# psu.net
KiCad netlist of a schematic drawn in EAGLE
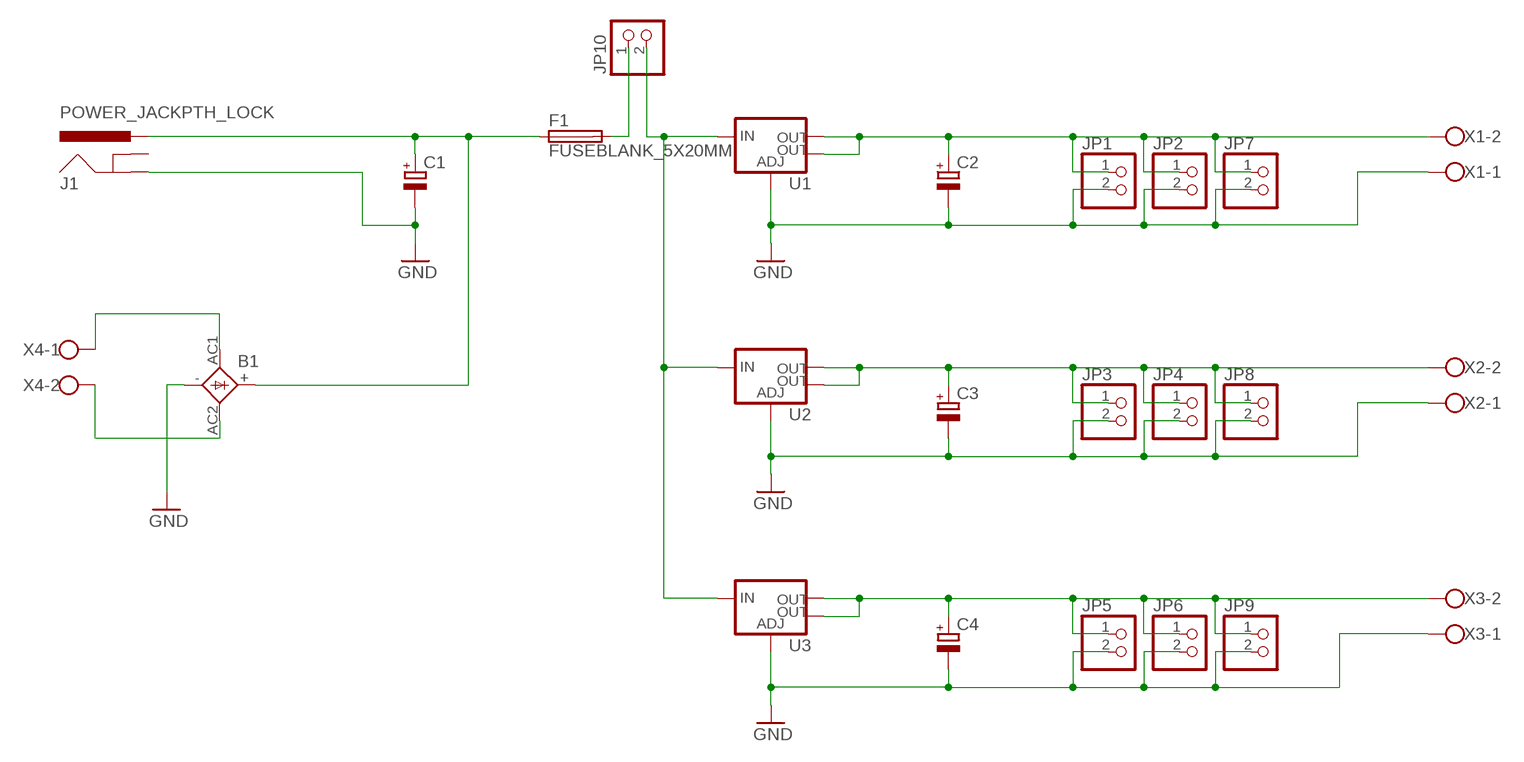
[diagram p0: schematic, sheet 1]

(export (version "E")
  (design (tool "Eeschema 10.0.6"))
  (components
    (comp (ref "B1")
      (value "KBU")
      (footprint "eagle-import:KBU")
      (libsource (lib "eagle-import") (part "KBU"))
    )
    (comp (ref "C1")
      (value "CPOL-EUE5-10.5")
      (footprint "eagle-import:E5-10,5")
      (libsource (lib "eagle-import") (part "resistor_CPOL-EUE5-10.5"))
    )
    (comp (ref "C2")
      (value "CPOL-EUE2.5-7")
      (footprint "eagle-import:E2,5-7")
      (libsource (lib "eagle-import") (part "CPOL-EUE2.5-7"))
    )
    (comp (ref "C3")
      (value "CPOL-EUE2.5-7")
      (footprint "eagle-import:E2,5-7")
      (libsource (lib "eagle-import") (part "CPOL-EUE2.5-7"))
    )
    (comp (ref "C4")
      (value "CPOL-EUE2.5-7")
      (footprint "eagle-import:E2,5-7")
      (libsource (lib "eagle-import") (part "CPOL-EUE2.5-7"))
    )
    (comp (ref "F1")
      (value "FUSEBLANK_5X20MM")
      (footprint "eagle-import:FUSE_HOLDER_5X20MM")
      (libsource (lib "eagle-import") (part "FUSEBLANK_5X20MM"))
    )
    (comp (ref "J1")
      (value "POWER_JACKPTH_LOCK")
      (footprint "eagle-import:POWER_JACK_PTH_LOCK")
      (libsource (lib "eagle-import") (part "POWER_JACKPTH_LOCK"))
    )
    (comp (ref "JP1")
      (value "PINHD-1X2")
      (footprint "eagle-import:1X02")
      (libsource (lib "eagle-import") (part "PINHD-1X2"))
    )
    (comp (ref "JP2")
      (value "PINHD-1X2")
      (footprint "eagle-import:1X02")
      (libsource (lib "eagle-import") (part "PINHD-1X2"))
    )
    (comp (ref "JP3")
      (value "PINHD-1X2")
      (footprint "eagle-import:1X02")
      (libsource (lib "eagle-import") (part "PINHD-1X2"))
    )
    (comp (ref "JP4")
      (value "PINHD-1X2")
      (footprint "eagle-import:1X02")
      (libsource (lib "eagle-import") (part "PINHD-1X2"))
    )
    (comp (ref "JP5")
      (value "PINHD-1X2")
      (footprint "eagle-import:1X02")
      (libsource (lib "eagle-import") (part "PINHD-1X2"))
    )
    (comp (ref "JP6")
      (value "PINHD-1X2")
      (footprint "eagle-import:1X02")
      (libsource (lib "eagle-import") (part "PINHD-1X2"))
    )
    (comp (ref "JP7")
      (value "PINHD-1X2")
      (footprint "eagle-import:1X02")
      (libsource (lib "eagle-import") (part "PINHD-1X2"))
    )
    (comp (ref "JP8")
      (value "PINHD-1X2")
      (footprint "eagle-import:1X02")
      (libsource (lib "eagle-import") (part "PINHD-1X2"))
    )
    (comp (ref "JP9")
      (value "PINHD-1X2")
      (footprint "eagle-import:1X02")
      (libsource (lib "eagle-import") (part "PINHD-1X2"))
    )
    (comp (ref "JP10")
      (value "PINHD-1X2")
      (footprint "eagle-import:1X02")
      (libsource (lib "eagle-import") (part "PINHD-1X2"))
    )
    (comp (ref "U1")
      (value "V_REG_LM1117SOT223")
      (footprint "eagle-import:SOT223")
      (libsource (lib "eagle-import") (part "V_REG_LM1117SOT223"))
    )
    (comp (ref "U2")
      (value "V_REG_LM1117SOT223")
      (footprint "eagle-import:SOT223")
      (libsource (lib "eagle-import") (part "V_REG_LM1117SOT223"))
    )
    (comp (ref "U3")
      (value "V_REG_LM1117SOT223")
      (footprint "eagle-import:SOT223")
      (libsource (lib "eagle-import") (part "V_REG_LM1117SOT223"))
    )
    (comp (ref "X1")
      (value "W237-102")
      (footprint "eagle-import:W237-102")
      (fields (field (name "MPN") "237-102"))
      (libsource (lib "eagle-import") (part "W237-102"))
    )
    (comp (ref "X2")
      (value "W237-102")
      (footprint "eagle-import:W237-102")
      (fields (field (name "MPN") "237-102"))
      (libsource (lib "eagle-import") (part "W237-102"))
    )
    (comp (ref "X3")
      (value "W237-102")
      (footprint "eagle-import:W237-102")
      (fields (field (name "MPN") "237-102"))
      (libsource (lib "eagle-import") (part "W237-102"))
    )
    (comp (ref "X4")
      (value "W237-102")
      (footprint "eagle-import:W237-102")
      (fields (field (name "MPN") "237-102"))
      (libsource (lib "eagle-import") (part "W237-102"))
    )
  )
  (nets
    (net (code "1") (name "GND") (class "Default")
      (node (ref "B1") (pin "-") (pinfunction "-_-") (pintype "passive"))
      (node (ref "C1") (pin "-") (pinfunction "-_-") (pintype "passive"))
      (node (ref "C2") (pin "-") (pinfunction "-_-") (pintype "passive"))
      (node (ref "C3") (pin "-") (pinfunction "-_-") (pintype "passive"))
      (node (ref "C4") (pin "-") (pinfunction "-_-") (pintype "passive"))
      (node (ref "J1") (pin "GND") (pinfunction "GND_GND") (pintype "bidirectional"))
      (node (ref "JP1") (pin "2") (pinfunction "2_2") (pintype "passive"))
      (node (ref "JP2") (pin "2") (pinfunction "2_2") (pintype "passive"))
      (node (ref "JP3") (pin "2") (pinfunction "2_2") (pintype "passive"))
      (node (ref "JP4") (pin "2") (pinfunction "2_2") (pintype "passive"))
      (node (ref "JP5") (pin "2") (pinfunction "2_2") (pintype "passive"))
      (node (ref "JP6") (pin "2") (pinfunction "2_2") (pintype "passive"))
      (node (ref "JP7") (pin "2") (pinfunction "2_2") (pintype "passive"))
      (node (ref "JP8") (pin "2") (pinfunction "2_2") (pintype "passive"))
      (node (ref "JP9") (pin "2") (pinfunction "2_2") (pintype "passive"))
      (node (ref "U1") (pin "1") (pinfunction "ADJ_1") (pintype "input"))
      (node (ref "U2") (pin "1") (pinfunction "ADJ_1") (pintype "input"))
      (node (ref "U3") (pin "1") (pinfunction "ADJ_1") (pintype "input"))
      (node (ref "X1") (pin "1") (pinfunction "KL_1") (pintype "passive"))
      (node (ref "X2") (pin "1") (pinfunction "KL_1") (pintype "passive"))
      (node (ref "X3") (pin "1") (pinfunction "KL_1") (pintype "passive"))
    )
    (net (code "2") (name "Net-(B1-Pad+)") (class "Default")
      (node (ref "B1") (pin "+") (pinfunction "+_+") (pintype "passive"))
      (node (ref "C1") (pin "+") (pinfunction "+_+") (pintype "passive"))
      (node (ref "F1") (pin "1") (pinfunction "1_1") (pintype "passive"))
      (node (ref "J1") (pin "PWR") (pinfunction "PWR_PWR") (pintype "bidirectional"))
    )
    (net (code "3") (name "Net-(F1-Pad2)") (class "Default")
      (node (ref "F1") (pin "2") (pinfunction "2_2") (pintype "passive"))
      (node (ref "JP10") (pin "1") (pinfunction "1_1") (pintype "passive"))
    )
    (net (code "4") (name "Net-(U1-IN)") (class "Default")
      (node (ref "JP10") (pin "2") (pinfunction "2_2") (pintype "passive"))
      (node (ref "U1") (pin "3") (pinfunction "IN_3") (pintype "input"))
      (node (ref "U2") (pin "3") (pinfunction "IN_3") (pintype "input"))
      (node (ref "U3") (pin "3") (pinfunction "IN_3") (pintype "input"))
    )
    (net (code "5") (name "Net-(X1B-KL)") (class "Default")
      (node (ref "C2") (pin "+") (pinfunction "+_+") (pintype "passive"))
      (node (ref "JP1") (pin "1") (pinfunction "1_1") (pintype "passive"))
      (node (ref "JP2") (pin "1") (pinfunction "1_1") (pintype "passive"))
      (node (ref "JP7") (pin "1") (pinfunction "1_1") (pintype "passive"))
      (node (ref "U1") (pin "2") (pinfunction "OUT_2") (pintype "output"))
      (node (ref "U1") (pin "4") (pinfunction "OUT_4") (pintype "output"))
      (node (ref "X1") (pin "2") (pinfunction "KL_2") (pintype "passive"))
    )
    (net (code "6") (name "Net-(X2B-KL)") (class "Default")
      (node (ref "C3") (pin "+") (pinfunction "+_+") (pintype "passive"))
      (node (ref "JP3") (pin "1") (pinfunction "1_1") (pintype "passive"))
      (node (ref "JP4") (pin "1") (pinfunction "1_1") (pintype "passive"))
      (node (ref "JP8") (pin "1") (pinfunction "1_1") (pintype "passive"))
      (node (ref "U2") (pin "2") (pinfunction "OUT_2") (pintype "output"))
      (node (ref "U2") (pin "4") (pinfunction "OUT_4") (pintype "output"))
      (node (ref "X2") (pin "2") (pinfunction "KL_2") (pintype "passive"))
    )
    (net (code "7") (name "Net-(X3B-KL)") (class "Default")
      (node (ref "C4") (pin "+") (pinfunction "+_+") (pintype "passive"))
      (node (ref "JP5") (pin "1") (pinfunction "1_1") (pintype "passive"))
      (node (ref "JP6") (pin "1") (pinfunction "1_1") (pintype "passive"))
      (node (ref "JP9") (pin "1") (pinfunction "1_1") (pintype "passive"))
      (node (ref "U3") (pin "2") (pinfunction "OUT_2") (pintype "output"))
      (node (ref "U3") (pin "4") (pinfunction "OUT_4") (pintype "output"))
      (node (ref "X3") (pin "2") (pinfunction "KL_2") (pintype "passive"))
    )
    (net (code "8") (name "Net-(X4A-KL)") (class "Default")
      (node (ref "B1") (pin "AC1") (pinfunction "AC1_AC1") (pintype "passive"))
      (node (ref "X4") (pin "1") (pinfunction "KL_1") (pintype "passive"))
    )
    (net (code "9") (name "Net-(X4B-KL)") (class "Default")
      (node (ref "B1") (pin "AC2") (pinfunction "AC2_AC2") (pintype "passive"))
      (node (ref "X4") (pin "2") (pinfunction "KL_2") (pintype "passive"))
    )
    (net (code "10") (name "unconnected-(J1-PadGNDBREAK)") (class "Default")
      (node (ref "J1") (pin "GNDBREAK") (pinfunction "GNDBREAK_GNDBREAK") (pintype "bidirectional"))
    )
  )
)
